# MCU.net
KiCad netlist of a schematic drawn in Altium Designer
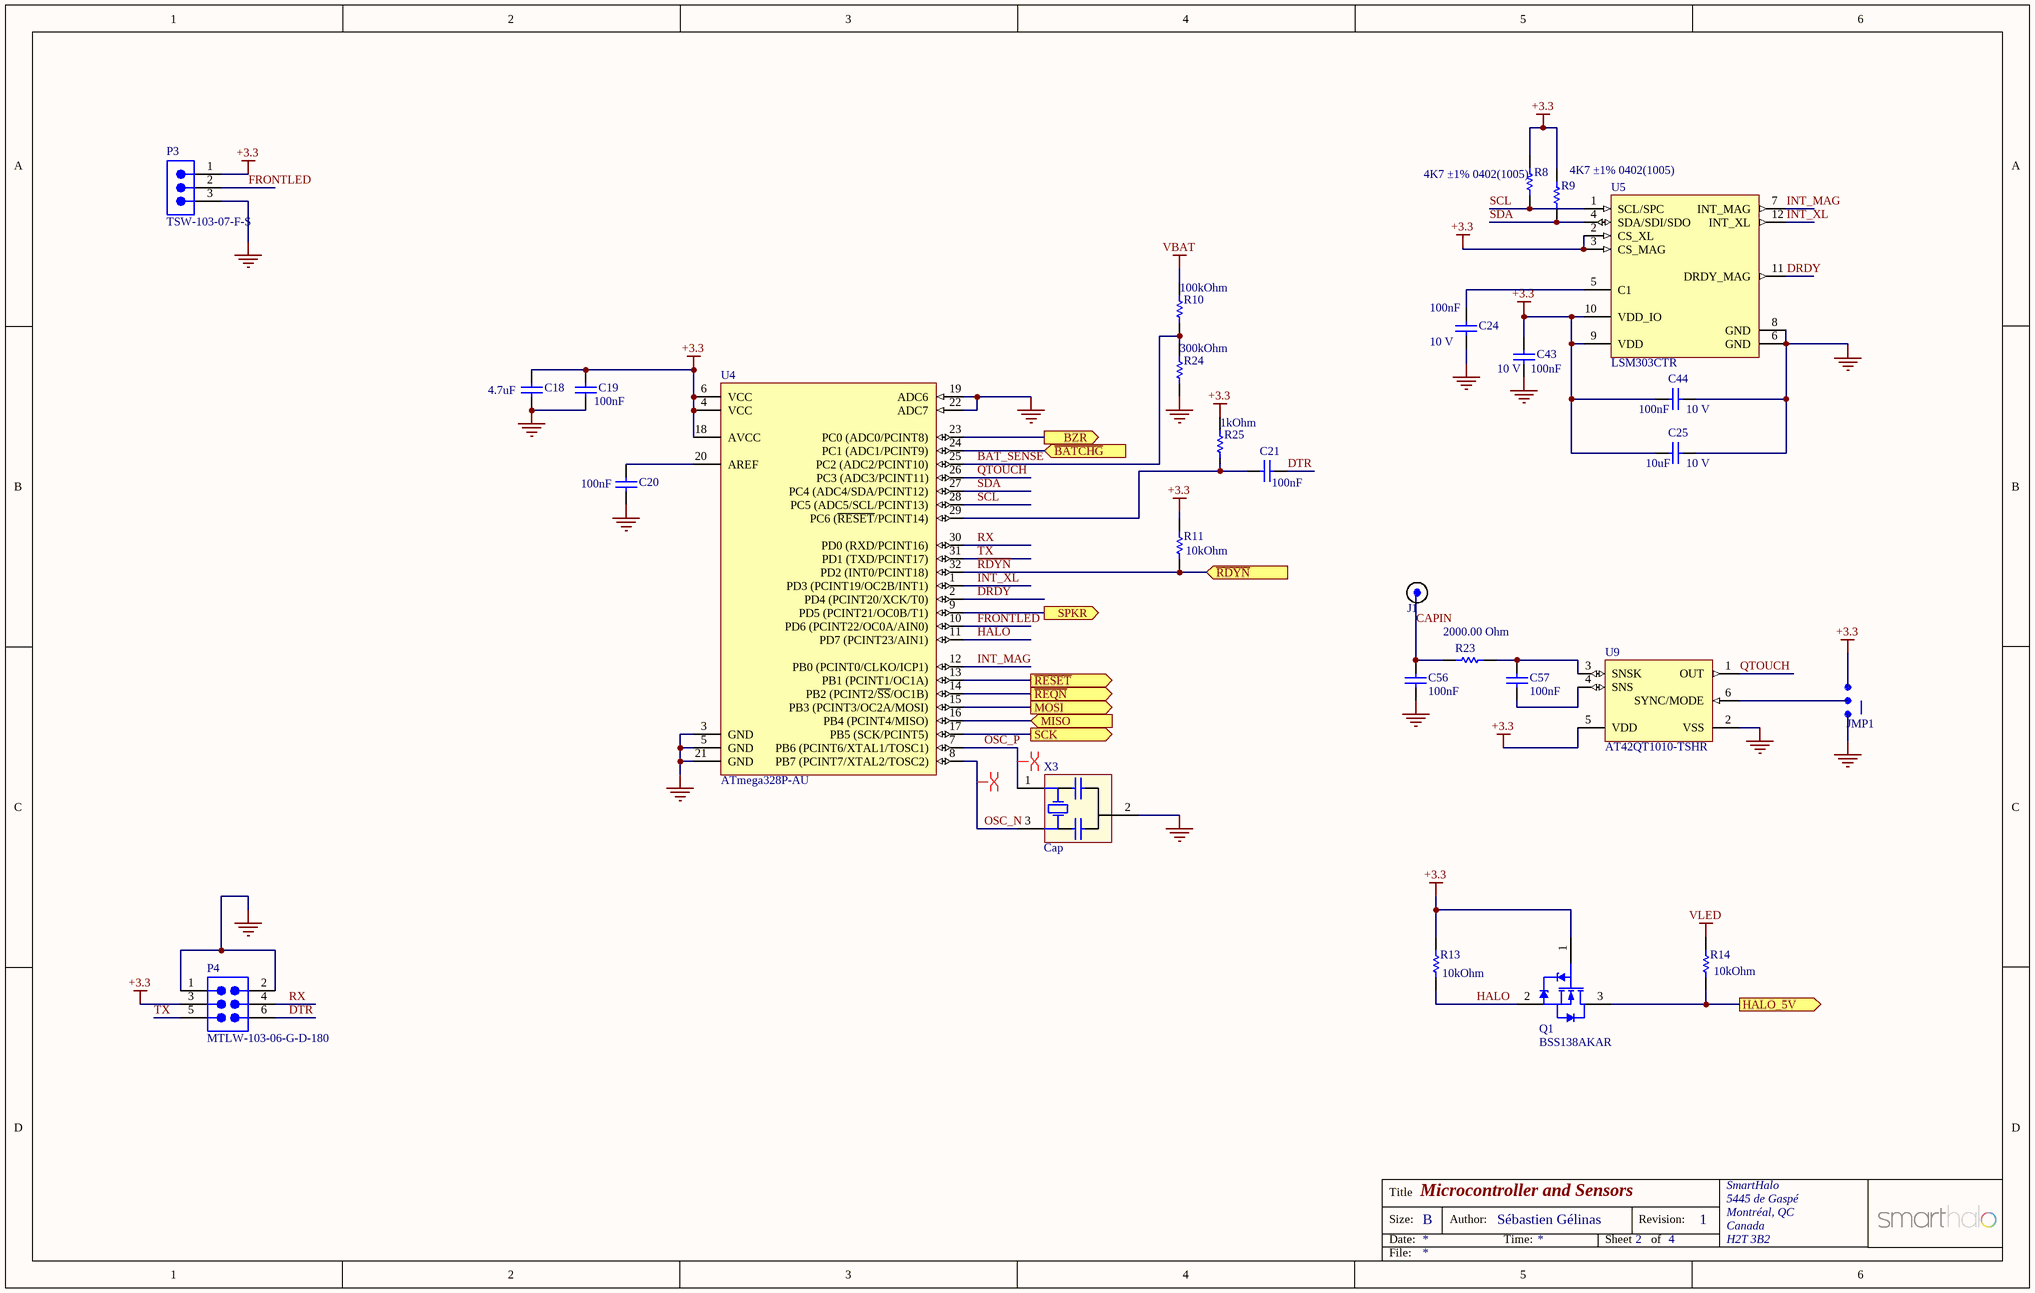
[diagram p0: MCU.SchDoc]

(export (version "E")
  (design (tool "Eeschema 10.0.6"))
  (components
    (comp (ref "C18")
      (value "CAP 4.7uF 10V 0603(1608)")
      (footprint "CAPC0603(1608)55_N")
      (description "CAP 4.7uF 10V ±10% 0603 (1608 Metric)")
      (fields (field (name "TOLERANCE") "±10%") (field (name "CAPACITANCE") "4.7uF"))
      (libsource (lib "Altium Content Vault") (part "CMP-1035-02784-1"))
    )
    (comp (ref "C19")
      (value "CAP 100nF 10V 0402(1005)")
      (footprint "CAPC0402(1005)60_L")
      (description "CAP 100nF 10V ±5% 0402 (1005 Metric)")
      (fields (field (name "TOLERANCE") "±5%") (field (name "CAPACITANCE") "100nF"))
      (libsource (lib "Altium Content Vault") (part "CMP-1034-02064-1"))
    )
    (comp (ref "C20")
      (value "CAP 100nF 10V 0402(1005)")
      (footprint "CAPC0402(1005)60_L")
      (description "CAP 100nF 10V ±5% 0402 (1005 Metric)")
      (fields (field (name "TOLERANCE") "±5%") (field (name "CAPACITANCE") "100nF"))
      (libsource (lib "Altium Content Vault") (part "CMP-1034-02064-1"))
    )
    (comp (ref "C21")
      (value "CAP 100nF 6.3V 0402(1005)")
      (footprint "CAPC0402(1005)60_M")
      (description "CAP 100nF 6.3V ±5% 0402 (1005 Metric)")
      (fields (field (name "CAPACITANCE") "100nF") (field (name "TOLERANCE") "±5%"))
      (libsource (lib "Altium Content Vault") (part "CMP-1034-02060-1"))
    )
    (comp (ref "C24")
      (value "CAP 100nF 10V 0402(1005)")
      (footprint "CAPC0402(1005)60_L")
      (description "CAP 100nF 10V ±5% 0402 (1005 Metric)")
      (fields
        (field (name "TOLERANCE") "±5%")
        (field (name "CAPACITANCE") "100nF")
        (field (name "RATED VOLTAGE") "10 V")
      )
      (libsource (lib "Altium Content Vault") (part "CMP-1034-02064-1"))
    )
    (comp (ref "C25")
      (value "CAP 10uF 10V 0603(1608)")
      (footprint "CAPC0603(1608)100_N")
      (description "CAP 10uF 10V ±10% 0603 (1608 Metric)")
      (fields
        (field (name "TOLERANCE") "±10%")
        (field (name "RATED VOLTAGE") "10 V")
        (field (name "CAPACITANCE") "10uF")
      )
      (libsource (lib "Altium Content Vault") (part "CMP-1035-02799-1"))
    )
    (comp (ref "C43")
      (value "CAP 100nF 10V 0402(1005)")
      (footprint "CAPC0402(1005)60_L")
      (description "CAP 100nF 10V ±5% 0402 (1005 Metric)")
      (fields
        (field (name "TOLERANCE") "±5%")
        (field (name "CAPACITANCE") "100nF")
        (field (name "RATED VOLTAGE") "10 V")
      )
      (libsource (lib "Altium Content Vault") (part "CMP-1034-02064-1"))
    )
    (comp (ref "C44")
      (value "CAP 100nF 10V 0402(1005)")
      (footprint "CAPC0402(1005)60_L")
      (description "CAP 100nF 10V ±5% 0402 (1005 Metric)")
      (fields
        (field (name "TOLERANCE") "±5%")
        (field (name "CAPACITANCE") "100nF")
        (field (name "RATED VOLTAGE") "10 V")
      )
      (libsource (lib "Altium Content Vault") (part "CMP-1034-02064-1"))
    )
    (comp (ref "C56")
      (value "CAP 100nF 10V 0402(1005)")
      (footprint "CAPC0402(1005)60_L")
      (description "CAP 100nF 10V ±5% 0402 (1005 Metric)")
      (fields (field (name "TOLERANCE") "±5%") (field (name "CAPACITANCE") "100nF"))
      (libsource (lib "Altium Content Vault") (part "CMP-1034-02064-1"))
    )
    (comp (ref "C57")
      (value "CAP 100nF 10V 0402(1005)")
      (footprint "CAPC0402(1005)60_L")
      (description "CAP 100nF 10V ±5% 0402 (1005 Metric)")
      (fields (field (name "TOLERANCE") "±5%") (field (name "CAPACITANCE") "100nF"))
      (libsource (lib "Altium Content Vault") (part "CMP-1034-02064-1"))
    )
    (comp (ref "J1")
      (value "HEADERPIN")
      (footprint "HEADERPIN")
      (description "HEADER 0.025\" PIN")
      (libsource (lib "SmartHalo_Symbols") (part "HEADERPIN"))
    )
    (comp (ref "JMP1")
      (value "JUMPER")
      (footprint "JUMPER_SMT")
      (libsource (lib "SmartHalo_Symbols") (part "JUMPER"))
    )
    (comp (ref "P3")
      (value "TSW-103-07-F-S")
      (footprint "SMTC-TSW-103-07-X-S")
      (description "0.025\" SQ Post Header, Through-hole, Vertical, -55 to 125 degC, 2.54 mm Pitch, 3-Pin, Male, RoHS")
      (fields (field (name "MANUFACTURER") "Samtec"))
      (libsource (lib "SmartHalo") (part "SMTC-TSW-103-X-X-S-X"))
    )
    (comp (ref "P4")
      (value "MTLW-103-06-G-D-180")
      (footprint "SMTC-MTLW-103-06-X-D-180")
      (fields (field (name "MANUFACTURER") "Samtec"))
      (libsource (lib "SmartHalo") (part "SMTC-MTLW-103-06-X-D-180"))
    )
    (comp (ref "Q1")
      (value "BSS138AKAR")
      (footprint "NXP-SOT23_N")
      (description "Single N-Channel Trench MOSFET, 60 V, 0.2 A, -55 to 150 degC, 3-Pin SOT23, Tape and Reel")
      (fields (field (name "MANUFACTURER") "NXP Semiconductors"))
      (libsource (lib "Altium Content Vault") (part "NXP-NMOS-GSD-3"))
    )
    (comp (ref "R8")
      (value "4K7 ±1% 0402(1005)")
      (footprint "RESC0402(1005)_N")
      (description "4K7 0.063W ±1% 0402 (1005 Metric)")
      (fields (field (name "POWER") "0.063 W") (field (name "TOLERANCE") "±1 %"))
      (libsource (lib "Altium Content Vault") (part "CMP-1011-00586-1"))
    )
    (comp (ref "R9")
      (value "4K7 ±1% 0402(1005)")
      (footprint "RESC0402(1005)_N")
      (description "4K7 0.063W ±1% 0402 (1005 Metric)")
      (fields (field (name "POWER") "0.063 W") (field (name "TOLERANCE") "±1 %"))
      (libsource (lib "Altium Content Vault") (part "CMP-1011-00586-1"))
    )
    (comp (ref "R10")
      (value "100K ±5% 0402(1005)")
      (footprint "RESC0402(1005)_L")
      (description "100K 0.063W ±5% 0402 (1005 Metric)")
      (fields
        (field (name "RESISTANCE") "100kOhm")
        (field (name "TOLERANCE") "±5 %")
        (field (name "POWER") "0.063 W")
      )
      (libsource (lib "Altium Content Vault") (part "CMP-1011-00074-1"))
    )
    (comp (ref "R11")
      (value "10K ±5% 0402(1005)")
      (footprint "RESC0402(1005)_N")
      (description "10K 0.063W ±5% 0402 (1005 Metric)")
      (fields
        (field (name "RESISTANCE") "10kOhm")
        (field (name "TOLERANCE") "±5 %")
        (field (name "POWER") "0.063 W")
      )
      (libsource (lib "Altium Content Vault") (part "CMP-1011-00098-1"))
    )
    (comp (ref "R13")
      (value "10K ±1% 0402(1005)")
      (footprint "RESC0402(1005)_N")
      (description "10K 0.063W ±1% 0402 (1005 Metric)")
      (fields
        (field (name "RESISTANCE") "10kOhm")
        (field (name "TOLERANCE") "±1 %")
        (field (name "POWER") "0.063 W")
      )
      (libsource (lib "Altium Content Vault") (part "CMP-1011-00623-1"))
    )
    (comp (ref "R14")
      (value "10K 1% 0402(1005)")
      (footprint "RESC0402(1005)_N")
      (description "10K 0.063W ±1% 0402 (1005 Metric)")
      (fields
        (field (name "RESISTANCE") "10kOhm")
        (field (name "TOLERANCE") "±1 %")
        (field (name "POWER") "0.063 W")
      )
      (libsource (lib "Altium Content Vault") (part "CMP-1011-00623-1"))
    )
    (comp (ref "R23")
      (value "2K ±5% 0603(1608)")
      (footprint "RESC0603(1608)_N")
      (description "2K 0.1W ±5% 0603 (1608 Metric)")
      (fields
        (field (name "TOLERANCE") "±5 %")
        (field (name "RESISTANCE") "2000.00 Ohm")
        (field (name "POWER") "0.1 W")
      )
      (libsource (lib "Altium Content Vault") (part "CMP-1012-00081-1"))
    )
    (comp (ref "R24")
      (value "300K ±5% 0402(1005)")
      (footprint "RESC0402(1005)_L")
      (description "300K 0.063W ±5% 0402 (1005 Metric)")
      (fields
        (field (name "RESISTANCE") "300kOhm")
        (field (name "TOLERANCE") "±5 %")
        (field (name "POWER") "0.063 W")
      )
      (libsource (lib "Altium Content Vault") (part "CMP-1011-00074-1"))
    )
    (comp (ref "R25")
      (value "1K ±5% 0402(1005)")
      (footprint "RESC0402(1005)_L")
      (description "1K 0.063W ±5% 0402 (1005 Metric)")
      (fields
        (field (name "RESISTANCE") "1kOhm")
        (field (name "TOLERANCE") "±5 %")
        (field (name "POWER") "0.063 W")
      )
      (libsource (lib "Altium Content Vault") (part "CMP-1011-00074-1"))
    )
    (comp (ref "U4")
      (value "ATmega328P-AU")
      (footprint "32A_M")
      (libsource (lib "SmartHalo") (part "MC-8B-ATM48-SQ32"))
    )
    (comp (ref "U5")
      (value "LSM303CTR")
      (footprint "SmartHalo:LGA12-2X2X1_N")
      (description "3D ACCELEROMETER/MAGNETOMETER")
      (libsource (lib "SmartHalo") (part "SEN-MOT-LSM303CTR-12"))
    )
    (comp (ref "U9")
      (value "AT42QT1010-TSHR")
      (footprint "6ST1_M")
      (description "One-channel Touch Sensor IC with Reset Timer, -40Â° to +85Â° C, 6-pin SOT23")
      (libsource (lib "Altium Content Vault") (part "IN-TSC-AT42QT1010-6"))
    )
    (comp (ref "X3")
      (value "Cap")
      (footprint "CSTCE10M0G55-R0")
      (description "CER RESONATOR 10.0MHZ SMD")
      (libsource (lib "SmartHalo") (part "CSTCE10M0G55-R0"))
    )
  )
  (nets
    (net (code "1") (name "+3.3") (class "Default")
      (node (ref "C18") (pin "2") (pinfunction "2_2") (pintype "passive"))
      (node (ref "C19") (pin "2") (pinfunction "2_2") (pintype "passive"))
      (node (ref "C25") (pin "2") (pinfunction "2_2") (pintype "passive"))
      (node (ref "C43") (pin "1") (pinfunction "1_1") (pintype "passive"))
      (node (ref "C44") (pin "2") (pinfunction "2_2") (pintype "passive"))
      (node (ref "JMP1") (pin "1") (pinfunction "1_1") (pintype "passive"))
      (node (ref "P3") (pin "1") (pinfunction "1_1") (pintype "passive"))
      (node (ref "P4") (pin "3") (pinfunction "3_3") (pintype "passive"))
      (node (ref "Q1") (pin "1") (pinfunction "G_1") (pintype "passive"))
      (node (ref "R11") (pin "2") (pinfunction "2_2") (pintype "passive"))
      (node (ref "R13") (pin "2") (pinfunction "2_2") (pintype "passive"))
      (node (ref "R25") (pin "2") (pinfunction "2_2") (pintype "passive"))
      (node (ref "R8") (pin "2") (pinfunction "2_2") (pintype "passive"))
      (node (ref "R9") (pin "2") (pinfunction "2_2") (pintype "passive"))
      (node (ref "U4") (pin "18") (pinfunction "AVCC_18") (pintype "power_in"))
      (node (ref "U4") (pin "4") (pinfunction "VCC_4") (pintype "power_in"))
      (node (ref "U4") (pin "6") (pinfunction "VCC_6") (pintype "power_in"))
      (node (ref "U5") (pin "10") (pinfunction "VDD_IO_10") (pintype "power_in"))
      (node (ref "U5") (pin "2") (pinfunction "CS_XL_2") (pintype "input"))
      (node (ref "U5") (pin "3") (pinfunction "CS_MAG_3") (pintype "input"))
      (node (ref "U5") (pin "9") (pinfunction "VDD_9") (pintype "power_in"))
      (node (ref "U9") (pin "5") (pinfunction "VDD_5") (pintype "power_in"))
    )
    (net (code "2") (name "/BAT_SENSE") (class "Default")
      (node (ref "R10") (pin "1") (pinfunction "1_1") (pintype "passive"))
      (node (ref "R24") (pin "2") (pinfunction "2_2") (pintype "passive"))
      (node (ref "U4") (pin "25") (pinfunction "PC2_(ADC2/PCINT10)_25") (pintype "bidirectional"))
    )
    (net (code "3") (name "/BZR") (class "Default")
      (node (ref "U4") (pin "23") (pinfunction "PC0_(ADC0/PCINT8)_23") (pintype "bidirectional"))
    )
    (net (code "4") (name "/CAPIN") (class "Default")
      (node (ref "C56") (pin "2") (pinfunction "2_2") (pintype "passive"))
      (node (ref "J1") (pin "1") (pinfunction "1_1") (pintype "passive"))
      (node (ref "R23") (pin "2") (pinfunction "2_2") (pintype "passive"))
    )
    (net (code "5") (name "/DRDY") (class "Default")
      (node (ref "U4") (pin "2") (pinfunction "PD4_(PCINT20/XCK/T0)_2") (pintype "bidirectional"))
      (node (ref "U5") (pin "11") (pinfunction "DRDY_MAG_11") (pintype "output"))
    )
    (net (code "6") (name "/DTR") (class "Default")
      (node (ref "C21") (pin "2") (pinfunction "2_2") (pintype "passive"))
      (node (ref "P4") (pin "6") (pinfunction "6_6") (pintype "passive"))
    )
    (net (code "7") (name "/FRONTLED") (class "Default")
      (node (ref "P3") (pin "2") (pinfunction "2_2") (pintype "passive"))
      (node (ref "U4") (pin "10") (pinfunction "PD6_(PCINT22/OC0A/AIN0)_10") (pintype "bidirectional"))
    )
    (net (code "8") (name "/HALO") (class "Default")
      (node (ref "Q1") (pin "2") (pinfunction "S_2") (pintype "passive"))
      (node (ref "R13") (pin "1") (pinfunction "1_1") (pintype "passive"))
      (node (ref "U4") (pin "11") (pinfunction "PD7_(PCINT23/AIN1)_11") (pintype "bidirectional"))
    )
    (net (code "9") (name "/HALO_5V") (class "Default")
      (node (ref "Q1") (pin "3") (pinfunction "D_3") (pintype "passive"))
      (node (ref "R14") (pin "1") (pinfunction "1_1") (pintype "passive"))
    )
    (net (code "10") (name "/INT_MAG") (class "Default")
      (node (ref "U4") (pin "12") (pinfunction "PB0_(PCINT0/CLKO/ICP1)_12") (pintype "bidirectional"))
      (node (ref "U5") (pin "7") (pinfunction "INT_MAG_7") (pintype "output"))
    )
    (net (code "11") (name "/INT_XL") (class "Default")
      (node (ref "U4") (pin "1") (pinfunction "PD3_(PCINT19/OC2B/INT1)_1") (pintype "bidirectional"))
      (node (ref "U5") (pin "12") (pinfunction "INT_XL_12") (pintype "output"))
    )
    (net (code "12") (name "/MISO") (class "Default")
      (node (ref "U4") (pin "16") (pinfunction "PB4_(PCINT4/MISO)_16") (pintype "bidirectional"))
    )
    (net (code "13") (name "/MOSI") (class "Default")
      (node (ref "U4") (pin "15") (pinfunction "PB3_(PCINT3/OC2A/MOSI)_15") (pintype "bidirectional"))
    )
    (net (code "14") (name "/OSC_N") (class "Default")
      (node (ref "U4") (pin "8") (pinfunction "PB7_(PCINT7/XTAL2/TOSC2)_8") (pintype "bidirectional"))
      (node (ref "X3") (pin "3") (pinfunction "C2_3") (pintype "passive"))
    )
    (net (code "15") (name "/OSC_P") (class "Default")
      (node (ref "U4") (pin "7") (pinfunction "PB6_(PCINT6/XTAL1/TOSC1)_7") (pintype "bidirectional"))
      (node (ref "X3") (pin "1") (pinfunction "C1_1") (pintype "passive"))
    )
    (net (code "16") (name "/QTOUCH") (class "Default")
      (node (ref "U4") (pin "26") (pinfunction "PC3_(ADC3/PCINT11)_26") (pintype "bidirectional"))
      (node (ref "U9") (pin "1") (pinfunction "OUT_1") (pintype "output"))
    )
    (net (code "17") (name "/RX") (class "Default")
      (node (ref "P4") (pin "4") (pinfunction "4_4") (pintype "passive"))
      (node (ref "U4") (pin "30") (pinfunction "PD0_(RXD/PCINT16)_30") (pintype "bidirectional"))
    )
    (net (code "18") (name "/SCK") (class "Default")
      (node (ref "U4") (pin "17") (pinfunction "PB5_(SCK/PCINT5)_17") (pintype "bidirectional"))
    )
    (net (code "19") (name "/SCL") (class "Default")
      (node (ref "R8") (pin "1") (pinfunction "1_1") (pintype "passive"))
      (node (ref "U4") (pin "28") (pinfunction "PC5_(ADC5/SCL/PCINT13)_28") (pintype "bidirectional"))
      (node (ref "U5") (pin "1") (pinfunction "SCL/SPC_1") (pintype "input"))
    )
    (net (code "20") (name "/SDA") (class "Default")
      (node (ref "R9") (pin "1") (pinfunction "1_1") (pintype "passive"))
      (node (ref "U4") (pin "27") (pinfunction "PC4_(ADC4/SDA/PCINT12)_27") (pintype "bidirectional"))
      (node (ref "U5") (pin "4") (pinfunction "SDA/SDI/SDO_4") (pintype "bidirectional"))
    )
    (net (code "21") (name "/SPKR") (class "Default")
      (node (ref "U4") (pin "9") (pinfunction "PD5_(PCINT21/OC0B/T1)_9") (pintype "bidirectional"))
    )
    (net (code "22") (name "/TX") (class "Default")
      (node (ref "P4") (pin "5") (pinfunction "5_5") (pintype "passive"))
      (node (ref "U4") (pin "31") (pinfunction "PD1_(TXD/PCINT17)_31") (pintype "bidirectional"))
    )
    (net (code "23") (name "/~{BATCHG}") (class "Default")
      (node (ref "U4") (pin "24") (pinfunction "PC1_(ADC1/PCINT9)_24") (pintype "bidirectional"))
    )
    (net (code "24") (name "/~{RDYN}") (class "Default")
      (node (ref "R11") (pin "1") (pinfunction "1_1") (pintype "passive"))
      (node (ref "U4") (pin "32") (pinfunction "PD2_(INT0/PCINT18)_32") (pintype "bidirectional"))
    )
    (net (code "25") (name "/~{REQN}") (class "Default")
      (node (ref "U4") (pin "14") (pinfunction "PB2_(PCINT2/~{SS}/OC1B)_14") (pintype "bidirectional"))
    )
    (net (code "26") (name "/~{RESET}") (class "Default")
      (node (ref "U4") (pin "13") (pinfunction "PB1_(PCINT1/OC1A)_13") (pintype "bidirectional"))
    )
    (net (code "27") (name "GND") (class "Default")
      (node (ref "C18") (pin "1") (pinfunction "1_1") (pintype "passive"))
      (node (ref "C19") (pin "1") (pinfunction "1_1") (pintype "passive"))
      (node (ref "C20") (pin "1") (pinfunction "1_1") (pintype "passive"))
      (node (ref "C24") (pin "2") (pinfunction "2_2") (pintype "passive"))
      (node (ref "C25") (pin "1") (pinfunction "1_1") (pintype "passive"))
      (node (ref "C43") (pin "2") (pinfunction "2_2") (pintype "passive"))
      (node (ref "C44") (pin "1") (pinfunction "1_1") (pintype "passive"))
      (node (ref "C56") (pin "1") (pinfunction "1_1") (pintype "passive"))
      (node (ref "JMP1") (pin "3") (pinfunction "3_3") (pintype "passive"))
      (node (ref "P3") (pin "3") (pinfunction "3_3") (pintype "passive"))
      (node (ref "P4") (pin "1") (pinfunction "1_1") (pintype "passive"))
      (node (ref "P4") (pin "2") (pinfunction "2_2") (pintype "passive"))
      (node (ref "R24") (pin "1") (pinfunction "1_1") (pintype "passive"))
      (node (ref "U4") (pin "19") (pinfunction "ADC6_19") (pintype "input"))
      (node (ref "U4") (pin "21") (pinfunction "GND_21") (pintype "power_in"))
      (node (ref "U4") (pin "22") (pinfunction "ADC7_22") (pintype "input"))
      (node (ref "U4") (pin "3") (pinfunction "GND_3") (pintype "power_in"))
      (node (ref "U4") (pin "5") (pinfunction "GND_5") (pintype "power_in"))
      (node (ref "U5") (pin "6") (pinfunction "GND_6") (pintype "power_in"))
      (node (ref "U5") (pin "8") (pinfunction "GND_8") (pintype "power_in"))
      (node (ref "U9") (pin "2") (pinfunction "VSS_2") (pintype "power_in"))
      (node (ref "X3") (pin "2") (pinfunction "GND_2") (pintype "power_in"))
    )
    (net (code "28") (name "Net-(U4-AREF)") (class "Default")
      (node (ref "C20") (pin "2") (pinfunction "2_2") (pintype "passive"))
      (node (ref "U4") (pin "20") (pinfunction "AREF_20") (pintype "passive"))
    )
    (net (code "29") (name "Net-(U4-PC6_(~{RESET}{slash}PCINT14))") (class "Default")
      (node (ref "C21") (pin "1") (pinfunction "1_1") (pintype "passive"))
      (node (ref "R25") (pin "1") (pinfunction "1_1") (pintype "passive"))
      (node (ref "U4") (pin "29") (pinfunction "PC6_(~{RESET}/PCINT14)_29") (pintype "bidirectional"))
    )
    (net (code "30") (name "Net-(U5-C1)") (class "Default")
      (node (ref "C24") (pin "1") (pinfunction "1_1") (pintype "passive"))
      (node (ref "U5") (pin "5") (pinfunction "C1_5") (pintype "passive"))
    )
    (net (code "31") (name "Net-(U9-SNS)") (class "Default")
      (node (ref "C57") (pin "1") (pinfunction "1_1") (pintype "passive"))
      (node (ref "U9") (pin "4") (pinfunction "SNS_4") (pintype "bidirectional"))
    )
    (net (code "32") (name "Net-(U9-SNSK)") (class "Default")
      (node (ref "C57") (pin "2") (pinfunction "2_2") (pintype "passive"))
      (node (ref "R23") (pin "1") (pinfunction "1_1") (pintype "passive"))
      (node (ref "U9") (pin "3") (pinfunction "SNSK_3") (pintype "bidirectional"))
    )
    (net (code "33") (name "Net-(U9-SYNC{slash}MODE)") (class "Default")
      (node (ref "JMP1") (pin "2") (pinfunction "2_2") (pintype "passive"))
      (node (ref "U9") (pin "6") (pinfunction "SYNC/MODE_6") (pintype "input"))
    )
    (net (code "34") (name "VBAT") (class "Default")
      (node (ref "R10") (pin "2") (pinfunction "2_2") (pintype "passive"))
    )
    (net (code "35") (name "VLED") (class "Default")
      (node (ref "R14") (pin "2") (pinfunction "2_2") (pintype "passive"))
    )
  )
)
